# ESQ_CONTROL_ESDV2_0.net
KiCad netlist of a schematic drawn in EAGLE
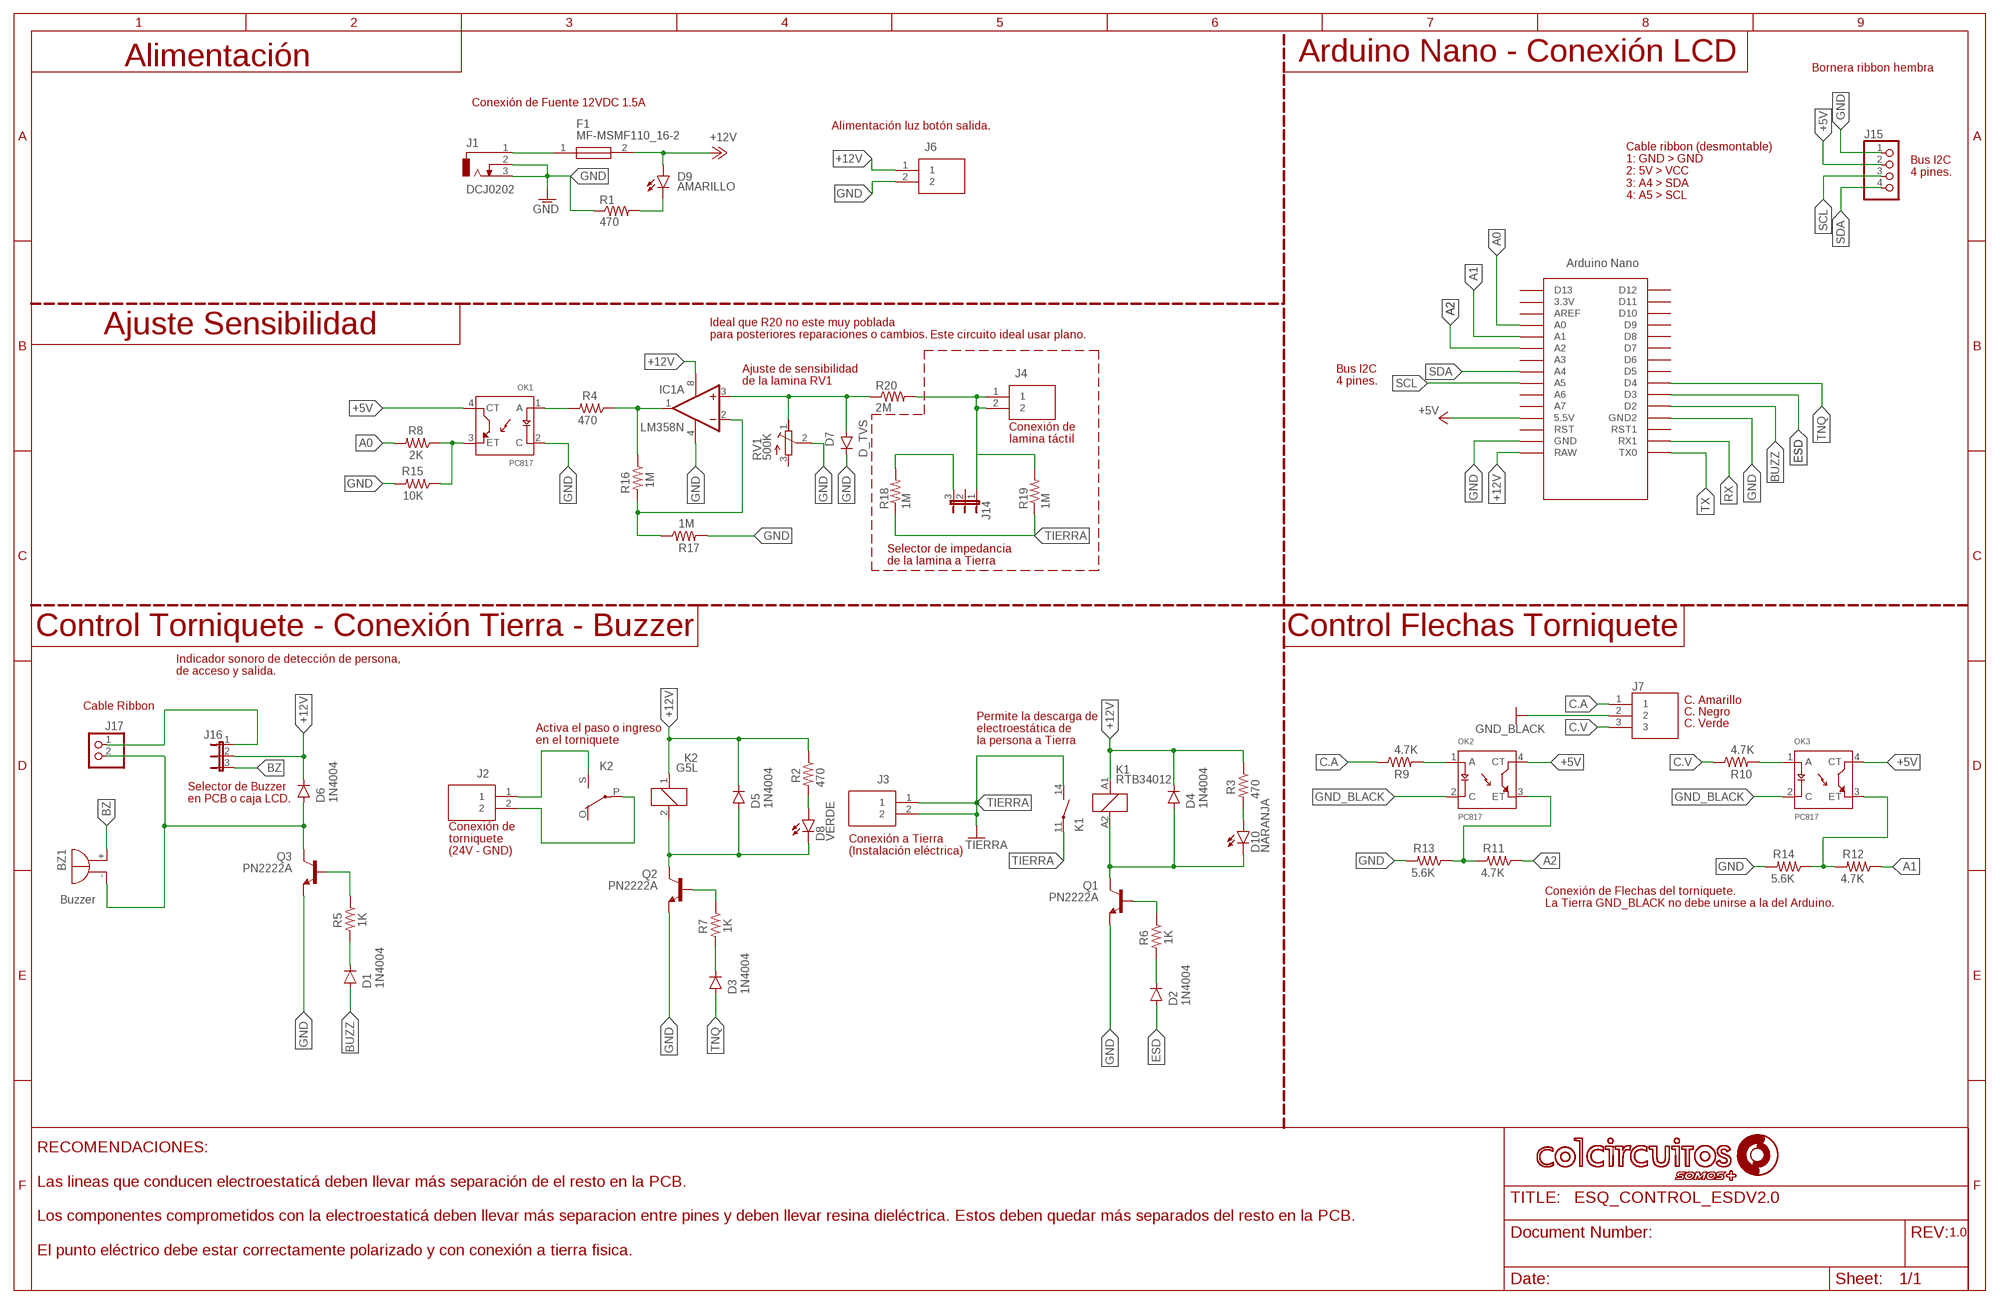
[diagram p0: schematic, sheet 1]

(export (version "E")
  (design (tool "Eeschema 10.0.6"))
  (components
    (comp (ref "BZ1")
      (value "Buzzer")
      (footprint "eagle-import:EB2209A")
      (libsource (lib "eagle-import") (part "EB2209A"))
    )
    (comp (ref "D1")
      (value "1N4004")
      (footprint "eagle-import:DO41-10")
      (libsource (lib "eagle-import") (part "1N4004"))
    )
    (comp (ref "D2")
      (value "1N4004")
      (footprint "eagle-import:DO41-10")
      (libsource (lib "eagle-import") (part "1N4004"))
    )
    (comp (ref "D3")
      (value "1N4004")
      (footprint "eagle-import:DO41-10")
      (libsource (lib "eagle-import") (part "1N4004"))
    )
    (comp (ref "D4")
      (value "1N4004")
      (footprint "eagle-import:DO41-10")
      (libsource (lib "eagle-import") (part "1N4004"))
    )
    (comp (ref "D5")
      (value "1N4004")
      (footprint "eagle-import:DO41-10")
      (libsource (lib "eagle-import") (part "1N4004"))
    )
    (comp (ref "D6")
      (value "1N4004")
      (footprint "eagle-import:DO41-10")
      (libsource (lib "eagle-import") (part "1N4004"))
    )
    (comp (ref "D7")
      (value "D_TVS")
      (footprint "eagle-import:DO214AC")
      (libsource (lib "eagle-import") (part "DIODE-DO214AC"))
    )
    (comp (ref "D8")
      (value "VERDE")
      (footprint "eagle-import:LED5MM")
      (libsource (lib "eagle-import") (part "LED5MM"))
    )
    (comp (ref "D9")
      (value "AMARILLO")
      (footprint "eagle-import:LED5MM")
      (libsource (lib "eagle-import") (part "LED5MM"))
    )
    (comp (ref "D10")
      (value "NARANJA")
      (footprint "eagle-import:LED5MM")
      (libsource (lib "eagle-import") (part "LED5MM"))
    )
    (comp (ref "F1")
      (value "MF-MSMF110_16-2")
      (footprint "eagle-import:FUSC4632X85N")
      (fields
        (field (name "ARROW_PART_NUMBER") "MF-MSMF110/16-2")
        (field (name "MOUSER_PART_NUMBER") "652-MF-MSMF110/16-2")
      )
      (libsource (lib "eagle-import") (part "MF-MSMF110_16-2"))
    )
    (comp (ref "IC1")
      (value "LM358N")
      (footprint "eagle-import:DIL08")
      (libsource (lib "eagle-import") (part "LM358N"))
    )
    (comp (ref "J1")
      (value "DCJ0202")
      (footprint "eagle-import:DCJ0202")
      (libsource (lib "eagle-import") (part "DCJ0202"))
    )
    (comp (ref "J2")
      (value "20020107-H021A01LF")
      (footprint "eagle-import:SHDR2W100P0X508_1X2_1216X850X1")
      (fields (field (name "MOUSER_PART_NUMBER") "649-220107-H021A01LF"))
      (libsource (lib "eagle-import") (part "20020107-H021A01LF"))
    )
    (comp (ref "J3")
      (value "20020107-H021A01LF")
      (footprint "eagle-import:SHDR2W100P0X508_1X2_1216X850X1")
      (fields (field (name "MOUSER_PART_NUMBER") "649-220107-H021A01LF"))
      (libsource (lib "eagle-import") (part "20020107-H021A01LF"))
    )
    (comp (ref "J4")
      (value "20020107-H021A01LF")
      (footprint "eagle-import:SHDR2W100P0X508_1X2_1216X850X1")
      (fields (field (name "MOUSER_PART_NUMBER") "649-220107-H021A01LF"))
      (libsource (lib "eagle-import") (part "20020107-H021A01LF"))
    )
    (comp (ref "J6")
      (value "20020107-H021A01LF")
      (footprint "eagle-import:SHDR2W100P0X508_1X2_1216X850X1")
      (fields (field (name "MOUSER_PART_NUMBER") "649-220107-H021A01LF"))
      (libsource (lib "eagle-import") (part "20020107-H021A01LF"))
    )
    (comp (ref "J7")
      (value "691311500103")
      (footprint "eagle-import:SHDR3W100P0X508_1X3_1724X850X1")
      (fields (field (name "MOUSER_PART_NUMBER") "710-691311500103"))
      (libsource (lib "eagle-import") (part "691311500103"))
    )
    (comp (ref "J14")
      (value "JP2E")
      (footprint "eagle-import:JP2")
      (libsource (lib "eagle-import") (part "JP2E"))
    )
    (comp (ref "J15")
      (value "PINHD-1X4")
      (footprint "eagle-import:1X04")
      (libsource (lib "eagle-import") (part "PINHD-1X4"))
    )
    (comp (ref "J16")
      (value "JP2E")
      (footprint "eagle-import:JP2")
      (libsource (lib "eagle-import") (part "JP2E"))
    )
    (comp (ref "J17")
      (value "PINHD-1X2")
      (footprint "eagle-import:1X02")
      (libsource (lib "eagle-import") (part "PINHD-1X2"))
    )
    (comp (ref "K1")
      (value "RTB34012")
      (footprint "eagle-import:RT-N_O12A3.5")
      (libsource (lib "eagle-import") (part "RT?B34012"))
    )
    (comp (ref "K2")
      (value "G5L")
      (footprint "eagle-import:G5LE")
      (libsource (lib "eagle-import") (part "G5L"))
    )
    (comp (ref "OK1")
      (value "PC817")
      (footprint "eagle-import:SOT254P975X400-4N")
      (fields (field (name "MF") "Sharp Microelectronics") (field (name "MP") "PC817X2NIP0F"))
      (libsource (lib "eagle-import") (part "PC817X2NIP0F"))
    )
    (comp (ref "OK2")
      (value "PC817")
      (footprint "eagle-import:SOT254P975X400-4N")
      (fields (field (name "MF") "Sharp Microelectronics") (field (name "MP") "PC817X2NIP0F"))
      (libsource (lib "eagle-import") (part "PC817X2NIP0F"))
    )
    (comp (ref "OK3")
      (value "PC817")
      (footprint "eagle-import:SOT254P975X400-4N")
      (fields (field (name "MF") "Sharp Microelectronics") (field (name "MP") "PC817X2NIP0F"))
      (libsource (lib "eagle-import") (part "PC817X2NIP0F"))
    )
    (comp (ref "Q1")
      (value "PN2222A")
      (footprint "eagle-import:TO92")
      (libsource (lib "eagle-import") (part "-NPN-TO92"))
    )
    (comp (ref "Q2")
      (value "PN2222A")
      (footprint "eagle-import:TO92")
      (libsource (lib "eagle-import") (part "-NPN-TO92"))
    )
    (comp (ref "Q3")
      (value "PN2222A")
      (footprint "eagle-import:TO92")
      (libsource (lib "eagle-import") (part "-NPN-TO92"))
    )
    (comp (ref "R1")
      (value "470")
      (footprint "eagle-import:R0805")
      (libsource (lib "eagle-import") (part "R-US_R0805"))
    )
    (comp (ref "R2")
      (value "470")
      (footprint "eagle-import:R0805")
      (libsource (lib "eagle-import") (part "R-US_R0805"))
    )
    (comp (ref "R3")
      (value "470")
      (footprint "eagle-import:R0805")
      (libsource (lib "eagle-import") (part "R-US_R0805"))
    )
    (comp (ref "R4")
      (value "470")
      (footprint "eagle-import:R0805")
      (libsource (lib "eagle-import") (part "R-US_R0805"))
    )
    (comp (ref "R5")
      (value "1K")
      (footprint "eagle-import:R0805")
      (libsource (lib "eagle-import") (part "R-US_R0805"))
    )
    (comp (ref "R6")
      (value "1K")
      (footprint "eagle-import:R0805")
      (libsource (lib "eagle-import") (part "R-US_R0805"))
    )
    (comp (ref "R7")
      (value "1K")
      (footprint "eagle-import:R0805")
      (libsource (lib "eagle-import") (part "R-US_R0805"))
    )
    (comp (ref "R8")
      (value "2K")
      (footprint "eagle-import:R0805")
      (libsource (lib "eagle-import") (part "R-US_R0805"))
    )
    (comp (ref "R9")
      (value "4.7K")
      (footprint "eagle-import:R0805")
      (libsource (lib "eagle-import") (part "R-US_R0805"))
    )
    (comp (ref "R10")
      (value "4.7K")
      (footprint "eagle-import:R0805")
      (libsource (lib "eagle-import") (part "R-US_R0805"))
    )
    (comp (ref "R11")
      (value "4.7K")
      (footprint "eagle-import:R0805")
      (libsource (lib "eagle-import") (part "R-US_R0805"))
    )
    (comp (ref "R12")
      (value "4.7K")
      (footprint "eagle-import:R0805")
      (libsource (lib "eagle-import") (part "R-US_R0805"))
    )
    (comp (ref "R13")
      (value "5.6K")
      (footprint "eagle-import:R0805")
      (libsource (lib "eagle-import") (part "R-US_R0805"))
    )
    (comp (ref "R14")
      (value "5.6K")
      (footprint "eagle-import:R0805")
      (libsource (lib "eagle-import") (part "R-US_R0805"))
    )
    (comp (ref "R15")
      (value "10K")
      (footprint "eagle-import:R0805")
      (libsource (lib "eagle-import") (part "R-US_R0805"))
    )
    (comp (ref "R16")
      (value "1M")
      (footprint "eagle-import:R0805")
      (libsource (lib "eagle-import") (part "R-US_R0805"))
    )
    (comp (ref "R17")
      (value "1M")
      (footprint "eagle-import:R0805")
      (libsource (lib "eagle-import") (part "R-US_R0805"))
    )
    (comp (ref "R18")
      (value "1M")
      (footprint "eagle-import:R1210")
      (libsource (lib "eagle-import") (part "R-US_R1210"))
    )
    (comp (ref "R19")
      (value "1M")
      (footprint "eagle-import:R1210")
      (libsource (lib "eagle-import") (part "R-US_R1210"))
    )
    (comp (ref "R20")
      (value "2M")
      (footprint "eagle-import:R1210")
      (libsource (lib "eagle-import") (part "R-US_R1210"))
    )
    (comp (ref "RV1")
      (value "500K")
      (footprint "eagle-import:RTRIMT93YA")
      (libsource (lib "eagle-import") (part "R-TRIMMT93YA"))
    )
    (comp (ref "U$1")
      (value "NANO")
      (footprint "eagle-import:NANO")
      (libsource (lib "eagle-import") (part "NANO"))
    )
  )
  (nets
    (net (code "1") (name "+5V") (class "Default")
      (node (ref "J15") (pin "2") (pinfunction "2_2") (pintype "passive"))
      (node (ref "OK1") (pin "4") (pinfunction "CT_4") (pintype "passive"))
      (node (ref "OK2") (pin "4") (pinfunction "CT_4") (pintype "passive"))
      (node (ref "OK3") (pin "4") (pinfunction "CT_4") (pintype "passive"))
      (node (ref "U$1") (pin "5V") (pinfunction "5.5V_5V") (pintype "bidirectional"))
    )
    (net (code "2") (name "+12V") (class "Default")
      (node (ref "D4") (pin "C") (pinfunction "C_C") (pintype "passive"))
      (node (ref "D5") (pin "C") (pinfunction "C_C") (pintype "passive"))
      (node (ref "D6") (pin "C") (pinfunction "C_C") (pintype "passive"))
      (node (ref "D9") (pin "A") (pinfunction "A_A") (pintype "passive"))
      (node (ref "F1") (pin "2") (pinfunction "2_2") (pintype "bidirectional"))
      (node (ref "IC1") (pin "8") (pinfunction "V+_8") (pintype "power_in"))
      (node (ref "J16") (pin "2") (pinfunction "2_2") (pintype "passive"))
      (node (ref "J6") (pin "1") (pinfunction "1_1") (pintype "bidirectional"))
      (node (ref "K1") (pin "A1") (pinfunction "1_A1") (pintype "passive"))
      (node (ref "K2") (pin "1") (pinfunction "1_1") (pintype "passive"))
      (node (ref "R2") (pin "1") (pinfunction "1_1") (pintype "passive"))
      (node (ref "R3") (pin "1") (pinfunction "1_1") (pintype "passive"))
      (node (ref "U$1") (pin "RAW") (pinfunction "RAW_RAW") (pintype "bidirectional"))
    )
    (net (code "3") (name "A0") (class "Default")
      (node (ref "R8") (pin "2") (pinfunction "2_2") (pintype "passive"))
      (node (ref "U$1") (pin "A0") (pinfunction "A0_A0") (pintype "bidirectional"))
    )
    (net (code "4") (name "A1") (class "Default")
      (node (ref "R12") (pin "1") (pinfunction "1_1") (pintype "passive"))
      (node (ref "U$1") (pin "A1") (pinfunction "A1_A1") (pintype "bidirectional"))
    )
    (net (code "5") (name "A2") (class "Default")
      (node (ref "R11") (pin "1") (pinfunction "1_1") (pintype "passive"))
      (node (ref "U$1") (pin "A2") (pinfunction "A2_A2") (pintype "bidirectional"))
    )
    (net (code "6") (name "BUZZ") (class "Default")
      (node (ref "D1") (pin "A") (pinfunction "A_A") (pintype "passive"))
      (node (ref "U$1") (pin "D2") (pinfunction "D2_D2") (pintype "bidirectional"))
    )
    (net (code "7") (name "BZ") (class "Default")
      (node (ref "BZ1") (pin "+") (pinfunction "+_+") (pintype "passive"))
      (node (ref "J16") (pin "3") (pinfunction "3_3") (pintype "passive"))
    )
    (net (code "8") (name "C.A") (class "Default")
      (node (ref "J7") (pin "1") (pinfunction "1_1") (pintype "bidirectional"))
      (node (ref "R9") (pin "1") (pinfunction "1_1") (pintype "passive"))
    )
    (net (code "9") (name "C.V") (class "Default")
      (node (ref "J7") (pin "3") (pinfunction "3_3") (pintype "bidirectional"))
      (node (ref "R10") (pin "1") (pinfunction "1_1") (pintype "passive"))
    )
    (net (code "10") (name "ESD") (class "Default")
      (node (ref "D2") (pin "A") (pinfunction "A_A") (pintype "passive"))
      (node (ref "U$1") (pin "D3") (pinfunction "D3_D3") (pintype "bidirectional"))
    )
    (net (code "11") (name "GND") (class "Default")
      (node (ref "D7") (pin "C") (pinfunction "C_C") (pintype "passive"))
      (node (ref "IC1") (pin "4") (pinfunction "V-_4") (pintype "power_in"))
      (node (ref "J1") (pin "2") (pinfunction "2_2") (pintype "passive"))
      (node (ref "J1") (pin "3") (pinfunction "3_3") (pintype "passive"))
      (node (ref "J15") (pin "1") (pinfunction "1_1") (pintype "passive"))
      (node (ref "J6") (pin "2") (pinfunction "2_2") (pintype "bidirectional"))
      (node (ref "OK1") (pin "2") (pinfunction "C_2") (pintype "passive"))
      (node (ref "Q1") (pin "1") (pinfunction "E_1") (pintype "passive"))
      (node (ref "Q2") (pin "1") (pinfunction "E_1") (pintype "passive"))
      (node (ref "Q3") (pin "1") (pinfunction "E_1") (pintype "passive"))
      (node (ref "R1") (pin "1") (pinfunction "1_1") (pintype "passive"))
      (node (ref "R13") (pin "2") (pinfunction "2_2") (pintype "passive"))
      (node (ref "R14") (pin "2") (pinfunction "2_2") (pintype "passive"))
      (node (ref "R15") (pin "2") (pinfunction "2_2") (pintype "passive"))
      (node (ref "R17") (pin "2") (pinfunction "2_2") (pintype "passive"))
      (node (ref "RV1") (pin "2") (pinfunction "S_2") (pintype "passive"))
      (node (ref "U$1") (pin "GND") (pinfunction "GND_GND") (pintype "bidirectional"))
      (node (ref "U$1") (pin "GND1") (pinfunction "GND2_GND1") (pintype "bidirectional"))
    )
    (net (code "12") (name "GND_BLACK") (class "Default")
      (node (ref "J7") (pin "2") (pinfunction "2_2") (pintype "bidirectional"))
      (node (ref "OK2") (pin "2") (pinfunction "C_2") (pintype "passive"))
      (node (ref "OK3") (pin "2") (pinfunction "C_2") (pintype "passive"))
    )
    (net (code "13") (name "Net-(D1-PadC)") (class "Default")
      (node (ref "D1") (pin "C") (pinfunction "C_C") (pintype "passive"))
      (node (ref "R5") (pin "2") (pinfunction "2_2") (pintype "passive"))
    )
    (net (code "14") (name "Net-(D2-PadC)") (class "Default")
      (node (ref "D2") (pin "C") (pinfunction "C_C") (pintype "passive"))
      (node (ref "R6") (pin "2") (pinfunction "2_2") (pintype "passive"))
    )
    (net (code "15") (name "Net-(D3-PadC)") (class "Default")
      (node (ref "D3") (pin "C") (pinfunction "C_C") (pintype "passive"))
      (node (ref "R7") (pin "2") (pinfunction "2_2") (pintype "passive"))
    )
    (net (code "16") (name "Net-(D8-C)") (class "Default")
      (node (ref "D5") (pin "A") (pinfunction "A_A") (pintype "passive"))
      (node (ref "D8") (pin "K") (pinfunction "C_K") (pintype "passive"))
      (node (ref "K2") (pin "2") (pinfunction "2_2") (pintype "passive"))
      (node (ref "Q2") (pin "3") (pinfunction "C_3") (pintype "passive"))
    )
    (net (code "17") (name "Net-(D8-PadA)") (class "Default")
      (node (ref "D8") (pin "A") (pinfunction "A_A") (pintype "passive"))
      (node (ref "R2") (pin "2") (pinfunction "2_2") (pintype "passive"))
    )
    (net (code "18") (name "Net-(D9-C)") (class "Default")
      (node (ref "D9") (pin "K") (pinfunction "C_K") (pintype "passive"))
      (node (ref "R1") (pin "2") (pinfunction "2_2") (pintype "passive"))
    )
    (net (code "19") (name "Net-(D10-C)") (class "Default")
      (node (ref "D10") (pin "K") (pinfunction "C_K") (pintype "passive"))
      (node (ref "D4") (pin "A") (pinfunction "A_A") (pintype "passive"))
      (node (ref "K1") (pin "A2") (pinfunction "2_A2") (pintype "passive"))
      (node (ref "Q1") (pin "3") (pinfunction "C_3") (pintype "passive"))
    )
    (net (code "20") (name "Net-(D10-PadA)") (class "Default")
      (node (ref "D10") (pin "A") (pinfunction "A_A") (pintype "passive"))
      (node (ref "R3") (pin "2") (pinfunction "2_2") (pintype "passive"))
    )
    (net (code "21") (name "Net-(F1-Pad1)") (class "Default")
      (node (ref "F1") (pin "1") (pinfunction "1_1") (pintype "bidirectional"))
      (node (ref "J1") (pin "1") (pinfunction "1_1") (pintype "passive"))
    )
    (net (code "22") (name "Net-(IC1A-+IN)") (class "Default")
      (node (ref "D7") (pin "A") (pinfunction "A_A") (pintype "passive"))
      (node (ref "IC1") (pin "3") (pinfunction "+IN_3") (pintype "input"))
      (node (ref "R20") (pin "1") (pinfunction "1_1") (pintype "passive"))
      (node (ref "RV1") (pin "1") (pinfunction "E_1") (pintype "passive"))
    )
    (net (code "23") (name "Net-(IC1A--IN)") (class "Default")
      (node (ref "IC1") (pin "2") (pinfunction "-IN_2") (pintype "input"))
      (node (ref "R16") (pin "2") (pinfunction "2_2") (pintype "passive"))
      (node (ref "R17") (pin "1") (pinfunction "1_1") (pintype "passive"))
    )
    (net (code "24") (name "Net-(IC1A-OUT)") (class "Default")
      (node (ref "IC1") (pin "1") (pinfunction "OUT_1") (pintype "output"))
      (node (ref "R16") (pin "1") (pinfunction "1_1") (pintype "passive"))
      (node (ref "R4") (pin "1") (pinfunction "1_1") (pintype "passive"))
    )
    (net (code "25") (name "Net-(J2-Pad1)") (class "Default")
      (node (ref "J2") (pin "1") (pinfunction "1_1") (pintype "bidirectional"))
      (node (ref "K2") (pin "S") (pinfunction "S_S") (pintype "passive"))
    )
    (net (code "26") (name "Net-(J2-Pad2)") (class "Default")
      (node (ref "J2") (pin "2") (pinfunction "2_2") (pintype "bidirectional"))
      (node (ref "K2") (pin "P") (pinfunction "P_P") (pintype "passive"))
    )
    (net (code "27") (name "Net-(J14-Pad1)") (class "Default")
      (node (ref "J14") (pin "1") (pinfunction "1_1") (pintype "passive"))
      (node (ref "J4") (pin "1") (pinfunction "1_1") (pintype "bidirectional"))
      (node (ref "J4") (pin "2") (pinfunction "2_2") (pintype "bidirectional"))
      (node (ref "R19") (pin "2") (pinfunction "2_2") (pintype "passive"))
      (node (ref "R20") (pin "2") (pinfunction "2_2") (pintype "passive"))
    )
    (net (code "28") (name "Net-(J14-Pad3)") (class "Default")
      (node (ref "J14") (pin "3") (pinfunction "3_3") (pintype "passive"))
      (node (ref "R18") (pin "2") (pinfunction "2_2") (pintype "passive"))
    )
    (net (code "29") (name "Net-(J16-Pad1)") (class "Default")
      (node (ref "J16") (pin "1") (pinfunction "1_1") (pintype "passive"))
      (node (ref "J17") (pin "1") (pinfunction "1_1") (pintype "passive"))
    )
    (net (code "30") (name "Net-(OK1-A)") (class "Default")
      (node (ref "OK1") (pin "1") (pinfunction "A_1") (pintype "passive"))
      (node (ref "R4") (pin "2") (pinfunction "2_2") (pintype "passive"))
    )
    (net (code "31") (name "Net-(OK1-ET)") (class "Default")
      (node (ref "OK1") (pin "3") (pinfunction "ET_3") (pintype "passive"))
      (node (ref "R15") (pin "1") (pinfunction "1_1") (pintype "passive"))
      (node (ref "R8") (pin "1") (pinfunction "1_1") (pintype "passive"))
    )
    (net (code "32") (name "Net-(OK2-A)") (class "Default")
      (node (ref "OK2") (pin "1") (pinfunction "A_1") (pintype "passive"))
      (node (ref "R9") (pin "2") (pinfunction "2_2") (pintype "passive"))
    )
    (net (code "33") (name "Net-(OK2-ET)") (class "Default")
      (node (ref "OK2") (pin "3") (pinfunction "ET_3") (pintype "passive"))
      (node (ref "R11") (pin "2") (pinfunction "2_2") (pintype "passive"))
      (node (ref "R13") (pin "1") (pinfunction "1_1") (pintype "passive"))
    )
    (net (code "34") (name "Net-(OK3-A)") (class "Default")
      (node (ref "OK3") (pin "1") (pinfunction "A_1") (pintype "passive"))
      (node (ref "R10") (pin "2") (pinfunction "2_2") (pintype "passive"))
    )
    (net (code "35") (name "Net-(OK3-ET)") (class "Default")
      (node (ref "OK3") (pin "3") (pinfunction "ET_3") (pintype "passive"))
      (node (ref "R12") (pin "2") (pinfunction "2_2") (pintype "passive"))
      (node (ref "R14") (pin "1") (pinfunction "1_1") (pintype "passive"))
    )
    (net (code "36") (name "Net-(Q1-B)") (class "Default")
      (node (ref "Q1") (pin "2") (pinfunction "B_2") (pintype "passive"))
      (node (ref "R6") (pin "1") (pinfunction "1_1") (pintype "passive"))
    )
    (net (code "37") (name "Net-(Q2-B)") (class "Default")
      (node (ref "Q2") (pin "2") (pinfunction "B_2") (pintype "passive"))
      (node (ref "R7") (pin "1") (pinfunction "1_1") (pintype "passive"))
    )
    (net (code "38") (name "Net-(Q3-B)") (class "Default")
      (node (ref "Q3") (pin "2") (pinfunction "B_2") (pintype "passive"))
      (node (ref "R5") (pin "1") (pinfunction "1_1") (pintype "passive"))
    )
    (net (code "39") (name "Net-(Q3-C)") (class "Default")
      (node (ref "BZ1") (pin "-") (pinfunction "-_-") (pintype "passive"))
      (node (ref "D6") (pin "A") (pinfunction "A_A") (pintype "passive"))
      (node (ref "J17") (pin "2") (pinfunction "2_2") (pintype "passive"))
      (node (ref "Q3") (pin "3") (pinfunction "C_3") (pintype "passive"))
    )
    (net (code "40") (name "RX") (class "Default")
      (node (ref "U$1") (pin "RX1") (pinfunction "RX1_RX1") (pintype "bidirectional"))
    )
    (net (code "41") (name "SCL") (class "Default")
      (node (ref "J15") (pin "3") (pinfunction "3_3") (pintype "passive"))
      (node (ref "U$1") (pin "A5") (pinfunction "A5_A5") (pintype "bidirectional"))
    )
    (net (code "42") (name "SDA") (class "Default")
      (node (ref "J15") (pin "4") (pinfunction "4_4") (pintype "passive"))
      (node (ref "U$1") (pin "A4") (pinfunction "A4_A4") (pintype "bidirectional"))
    )
    (net (code "43") (name "TIERRA") (class "Default")
      (node (ref "J3") (pin "1") (pinfunction "1_1") (pintype "bidirectional"))
      (node (ref "J3") (pin "2") (pinfunction "2_2") (pintype "bidirectional"))
      (node (ref "K1") (pin "11") (pinfunction "P_11") (pintype "passive"))
      (node (ref "K1") (pin "14") (pinfunction "S_14") (pintype "passive"))
      (node (ref "R18") (pin "1") (pinfunction "1_1") (pintype "passive"))
      (node (ref "R19") (pin "1") (pinfunction "1_1") (pintype "passive"))
    )
    (net (code "44") (name "TNQ") (class "Default")
      (node (ref "D3") (pin "A") (pinfunction "A_A") (pintype "passive"))
      (node (ref "U$1") (pin "D4") (pinfunction "D4_D4") (pintype "bidirectional"))
    )
    (net (code "45") (name "TX") (class "Default")
      (node (ref "U$1") (pin "TX0") (pinfunction "TX0_TX0") (pintype "bidirectional"))
    )
    (net (code "46") (name "unconnected-(J14-Pad2)") (class "Default")
      (node (ref "J14") (pin "2") (pinfunction "2_2") (pintype "passive"))
    )
    (net (code "47") (name "unconnected-(K2-PadO)") (class "Default")
      (node (ref "K2") (pin "O") (pinfunction "O_O") (pintype "passive"))
    )
    (net (code "48") (name "unconnected-(RV1-A-Pad3)") (class "Default")
      (node (ref "RV1") (pin "3") (pinfunction "A_3") (pintype "passive"))
    )
    (net (code "49") (name "unconnected-(U$1-Pad3.3V)") (class "Default")
      (node (ref "U$1") (pin "3.3V") (pinfunction "3.3V_3.3V") (pintype "bidirectional"))
    )
    (net (code "50") (name "unconnected-(U$1-PadA3)") (class "Default")
      (node (ref "U$1") (pin "A3") (pinfunction "A3_A3") (pintype "bidirectional"))
    )
    (net (code "51") (name "unconnected-(U$1-PadA6)") (class "Default")
      (node (ref "U$1") (pin "A6") (pinfunction "A6_A6") (pintype "bidirectional"))
    )
    (net (code "52") (name "unconnected-(U$1-PadA7)") (class "Default")
      (node (ref "U$1") (pin "A7") (pinfunction "A7_A7") (pintype "bidirectional"))
    )
    (net (code "53") (name "unconnected-(U$1-PadAREF)") (class "Default")
      (node (ref "U$1") (pin "AREF") (pinfunction "AREF_AREF") (pintype "bidirectional"))
    )
    (net (code "54") (name "unconnected-(U$1-PadD5)") (class "Default")
      (node (ref "U$1") (pin "D5") (pinfunction "D5_D5") (pintype "bidirectional"))
    )
    (net (code "55") (name "unconnected-(U$1-PadD6)") (class "Default")
      (node (ref "U$1") (pin "D6") (pinfunction "D6_D6") (pintype "bidirectional"))
    )
    (net (code "56") (name "unconnected-(U$1-PadD7)") (class "Default")
      (node (ref "U$1") (pin "D7") (pinfunction "D7_D7") (pintype "bidirectional"))
    )
    (net (code "57") (name "unconnected-(U$1-PadD8)") (class "Default")
      (node (ref "U$1") (pin "D8") (pinfunction "D8_D8") (pintype "bidirectional"))
    )
    (net (code "58") (name "unconnected-(U$1-PadD9)") (class "Default")
      (node (ref "U$1") (pin "D9") (pinfunction "D9_D9") (pintype "bidirectional"))
    )
    (net (code "59") (name "unconnected-(U$1-PadD10)") (class "Default")
      (node (ref "U$1") (pin "D10") (pinfunction "D10_D10") (pintype "bidirectional"))
    )
    (net (code "60") (name "unconnected-(U$1-PadD11)") (class "Default")
      (node (ref "U$1") (pin "D11") (pinfunction "D11_D11") (pintype "bidirectional"))
    )
    (net (code "61") (name "unconnected-(U$1-PadD12)") (class "Default")
      (node (ref "U$1") (pin "D12") (pinfunction "D12_D12") (pintype "bidirectional"))
    )
    (net (code "62") (name "unconnected-(U$1-PadD13)") (class "Default")
      (node (ref "U$1") (pin "D13") (pinfunction "D13_D13") (pintype "bidirectional"))
    )
    (net (code "63") (name "unconnected-(U$1-PadICSP1)") (class "Default")
      (node (ref "U$1") (pin "ICSP1") (pinfunction "ICSP1_ICSP1") (pintype "bidirectional"))
    )
    (net (code "64") (name "unconnected-(U$1-PadICSP2)") (class "Default")
      (node (ref "U$1") (pin "ICSP2") (pinfunction "ICSP2_ICSP2") (pintype "bidirectional"))
    )
    (net (code "65") (name "unconnected-(U$1-PadICSP3)") (class "Default")
      (node (ref "U$1") (pin "ICSP3") (pinfunction "ICSP3_ICSP3") (pintype "bidirectional"))
    )
    (net (code "66") (name "unconnected-(U$1-PadICSP4)") (class "Default")
      (node (ref "U$1") (pin "ICSP4") (pinfunction "ICSP4_ICSP4") (pintype "bidirectional"))
    )
    (net (code "67") (name "unconnected-(U$1-PadICSP5)") (class "Default")
      (node (ref "U$1") (pin "ICSP5") (pinfunction "ICSP5_ICSP5") (pintype "bidirectional"))
    )
    (net (code "68") (name "unconnected-(U$1-PadICSP6)") (class "Default")
      (node (ref "U$1") (pin "ICSP6") (pinfunction "ICSP6_ICSP6") (pintype "bidirectional"))
    )
    (net (code "69") (name "unconnected-(U$1-PadRST)") (class "Default")
      (node (ref "U$1") (pin "RST") (pinfunction "RST_RST") (pintype "bidirectional"))
    )
    (net (code "70") (name "unconnected-(U$1-PadRST1)") (class "Default")
      (node (ref "U$1") (pin "RST1") (pinfunction "RST1_RST1") (pintype "bidirectional"))
    )
  )
)
